# hacktor_watch2.net
KiCad netlist of a schematic drawn in EAGLE
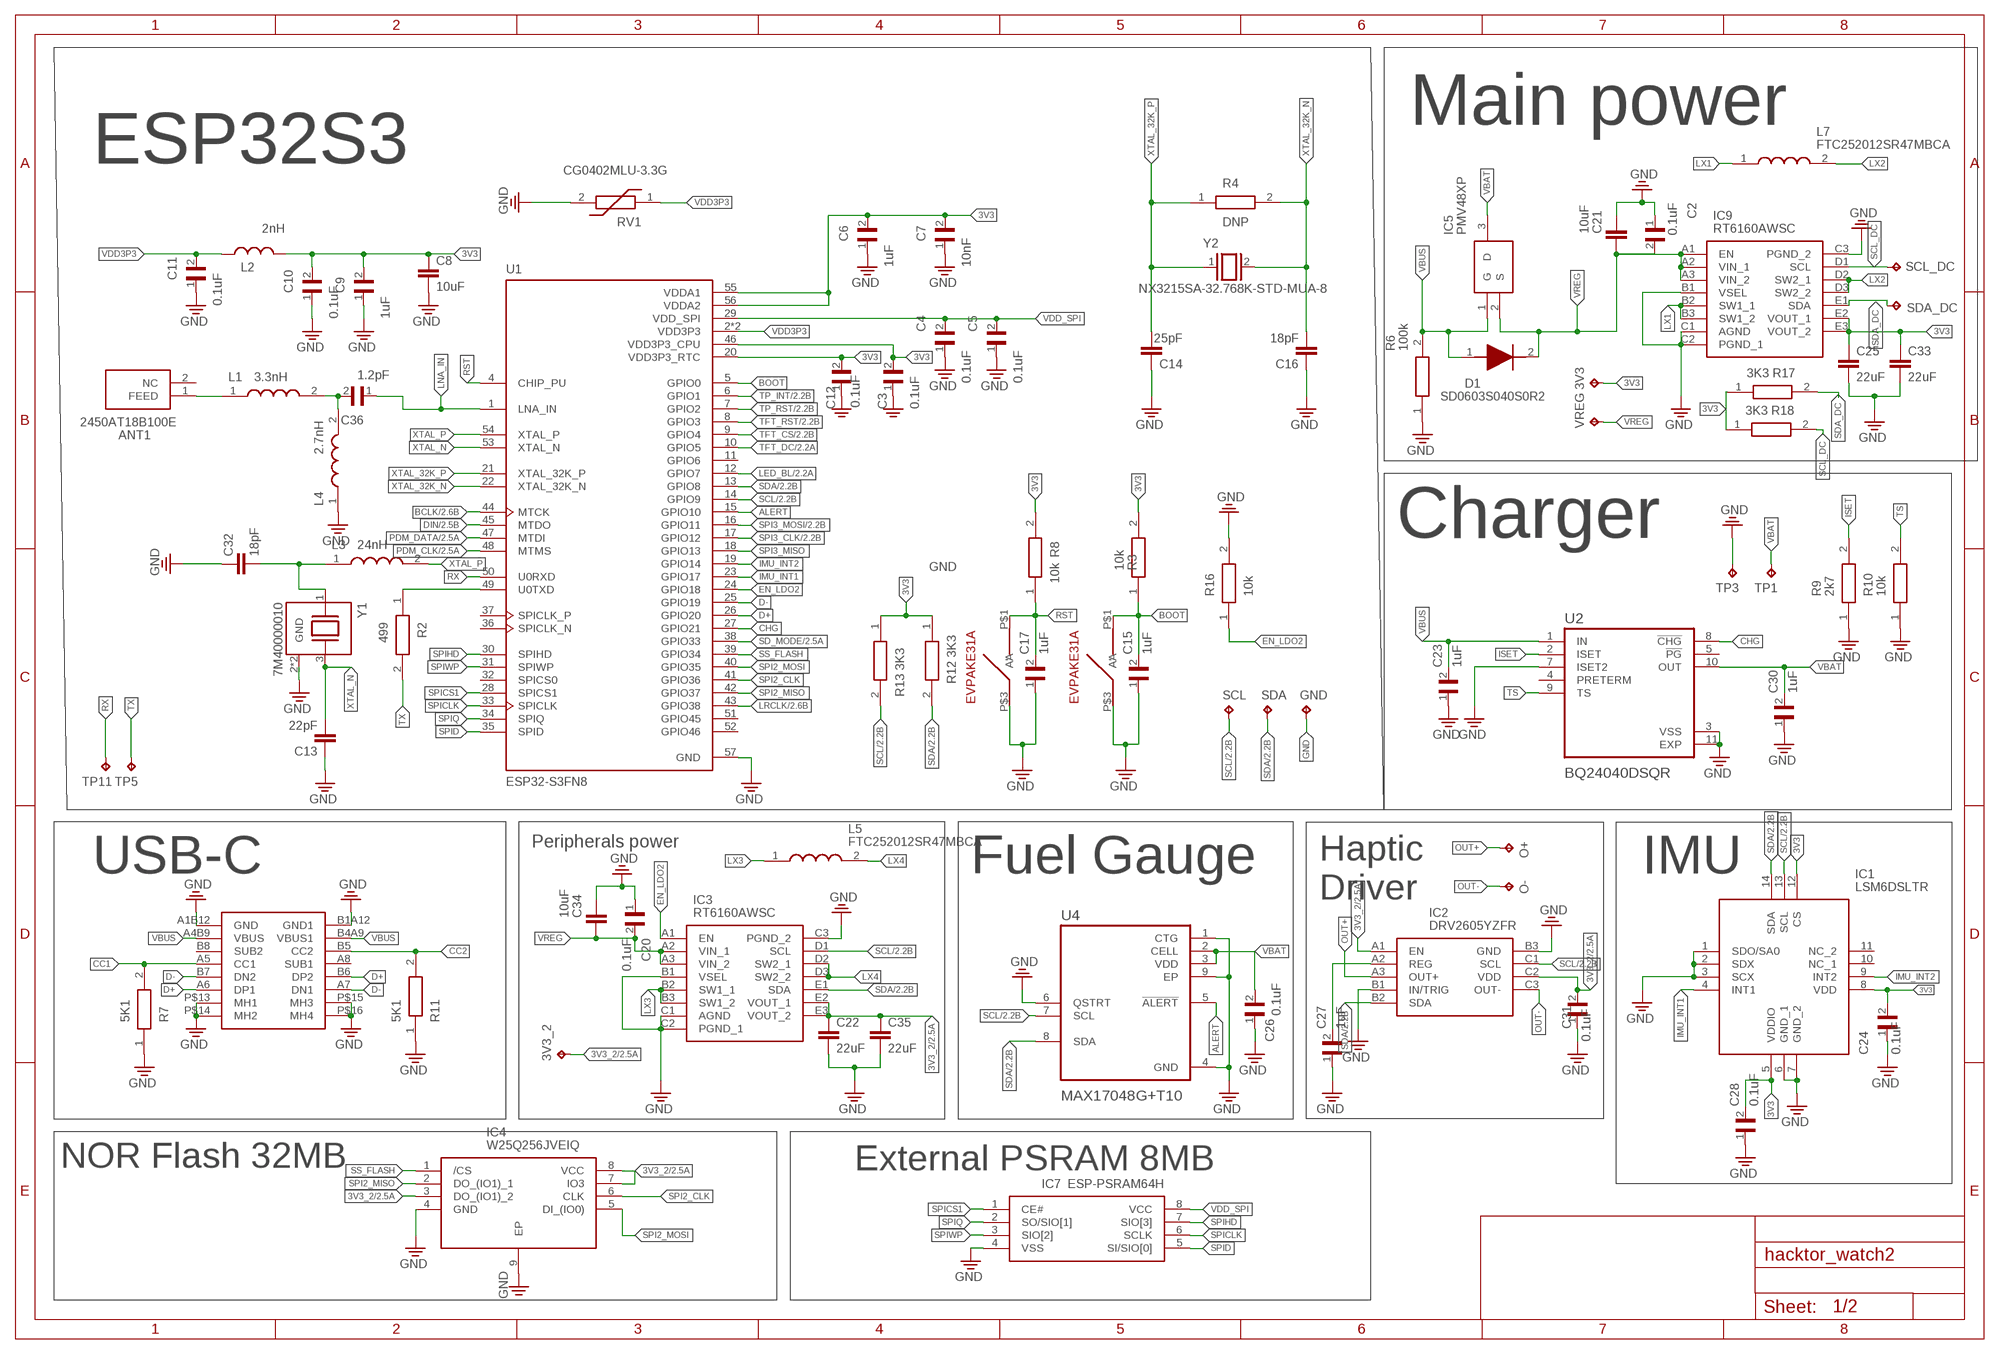
[diagram p0: schematic, sheet 1]
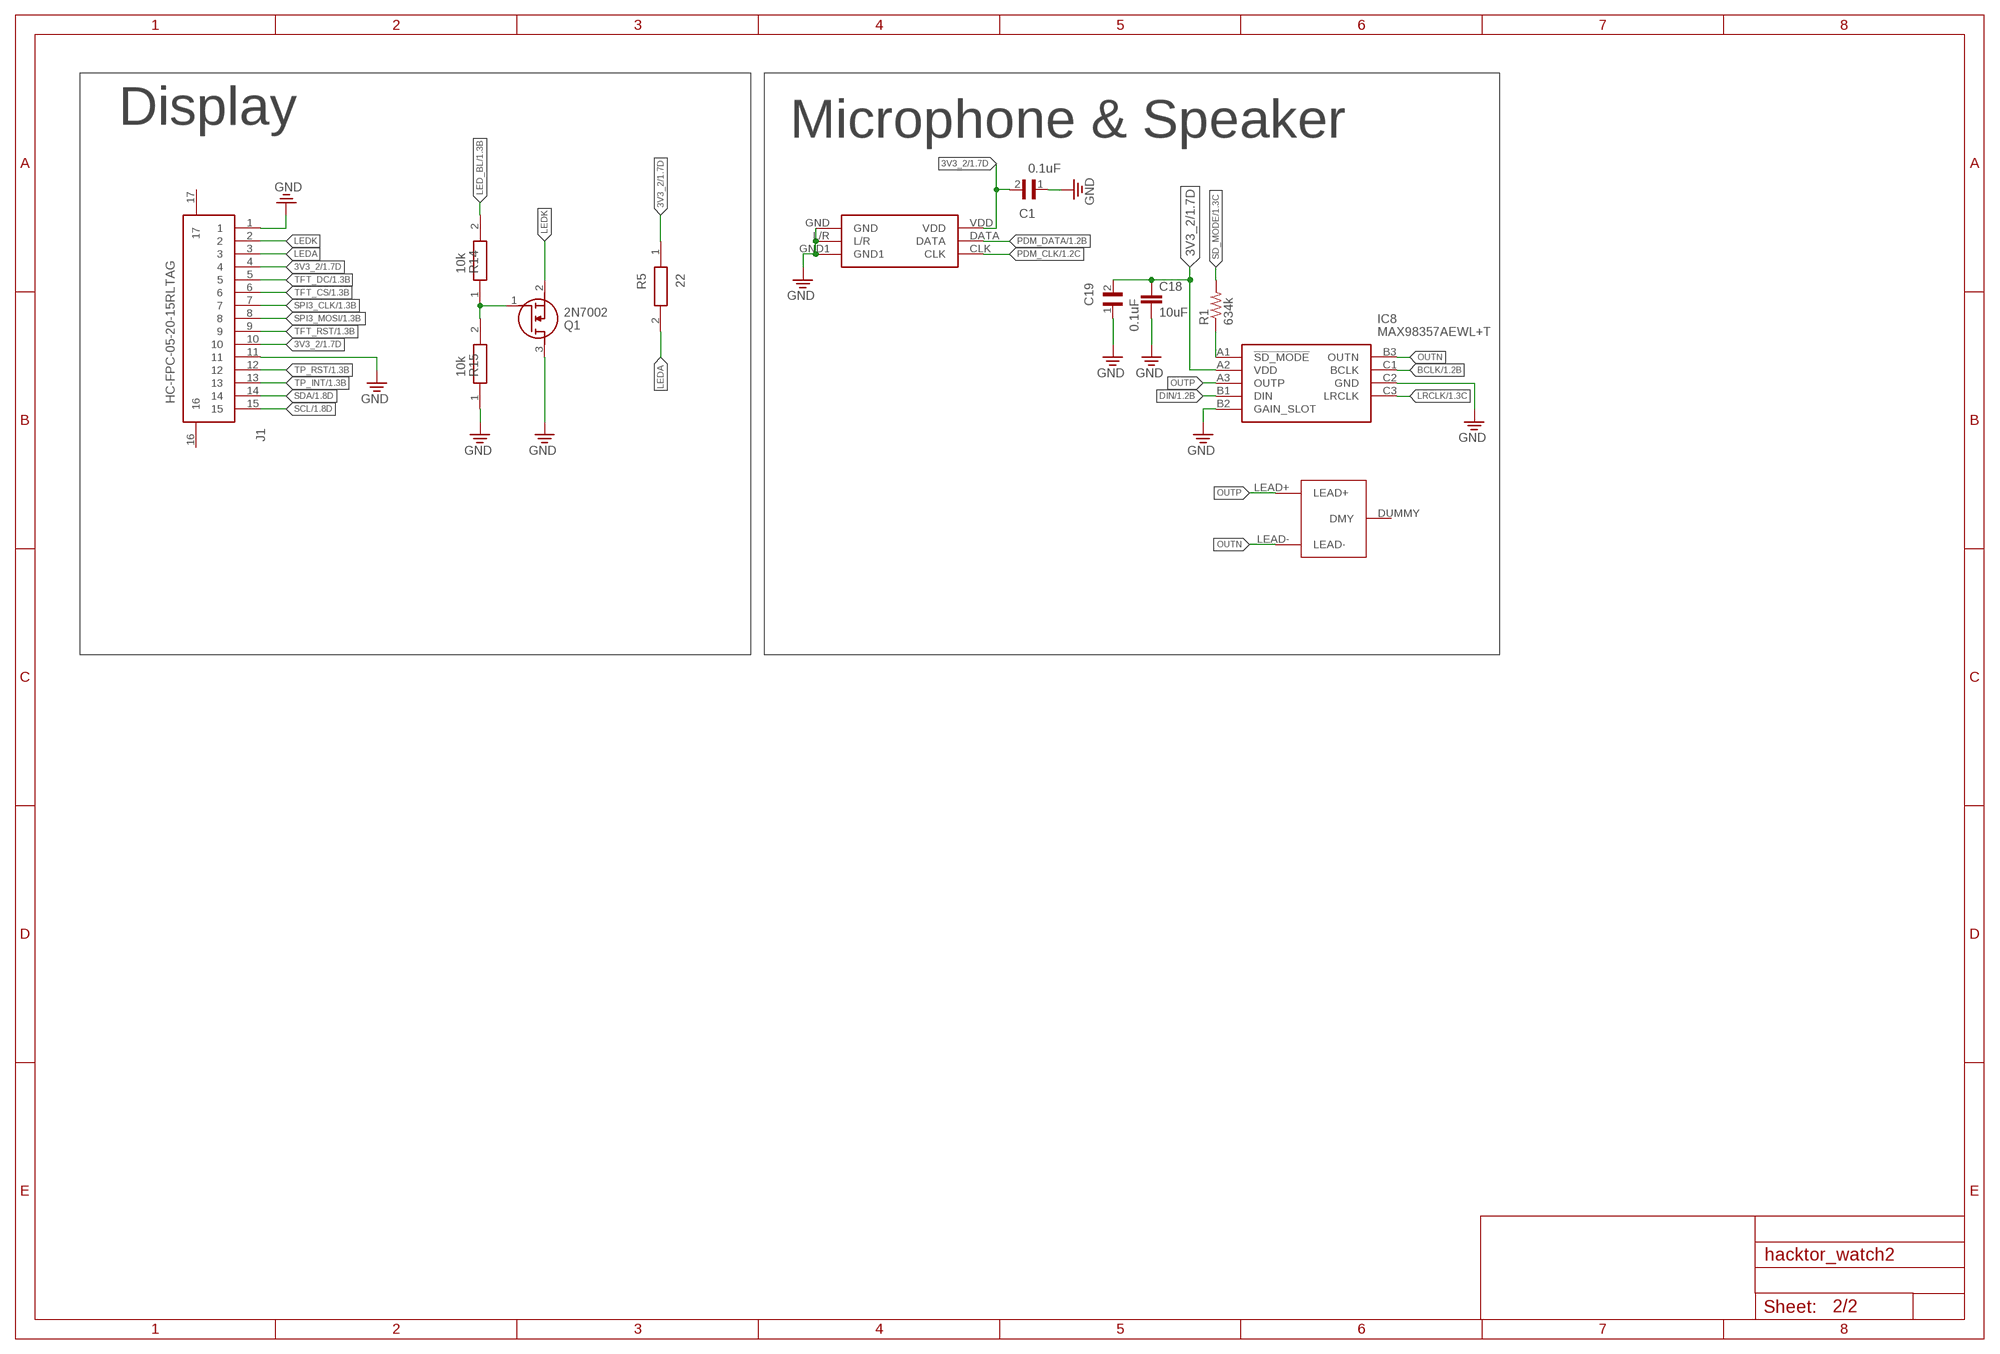
[diagram p1: schematic, sheet 2]

(export (version "E")
  (design (tool "Eeschema 10.0.6"))
  (components
    (comp (ref "C1")
      (value "0.1uF")
      (footprint "eagle-import:0201")
      (fields (field (name "SPICEPREFIX") "C"))
      (libsource (lib "eagle-import") (part "GRM011R60J152KE01L"))
    )
    (comp (ref "C18")
      (value "10uF")
      (footprint "eagle-import:0402")
      (libsource (lib "eagle-import") (part "CAP_0402"))
    )
    (comp (ref "C19")
      (value "0.1uF")
      (footprint "eagle-import:0201")
      (fields (field (name "SPICEPREFIX") "C"))
      (libsource (lib "eagle-import") (part "GRM011R60J152KE01L"))
    )
    (comp (ref "IC8")
      (value "MAX98357AEWL+T")
      (footprint "eagle-import:BGA9C40P3X3_144X135X69")
      (fields (field (name "MOUSER_PART_NUMBER") "700-MAX98357AEWL+T"))
      (libsource (lib "eagle-import") (part "MAX98357AEWL+T"))
    )
    (comp (ref "J1")
      (value "HC-FPC-05-20-15RLTAG")
      (footprint "eagle-import:HC-FPC-05-20-15RLTAG")
      (libsource (lib "eagle-import") (part "HC-FPC-05-20-15RLTAG"))
    )
    (comp (ref "Q1")
      (value "2N7002")
      (footprint "eagle-import:SOT96P240X120-3N")
      (fields (field (name "MOUSER_PART_NUMBER") "512-2N7002"))
      (libsource (lib "eagle-import") (part "2N7002"))
    )
    (comp (ref "R1")
      (value "634k")
      (footprint "eagle-import:0402")
      (libsource (lib "eagle-import") (part "RES_0402"))
    )
    (comp (ref "R5")
      (value "22")
      (footprint "eagle-import:0201")
      (fields (field (name "SPICEPREFIX") "R"))
      (libsource (lib "eagle-import") (part "CPF0201D7K68C1"))
    )
    (comp (ref "R14")
      (value "10k")
      (footprint "eagle-import:0201")
      (fields (field (name "SPICEPREFIX") "R"))
      (libsource (lib "eagle-import") (part "CPF0201D7K68C1"))
    )
    (comp (ref "R15")
      (value "10k")
      (footprint "eagle-import:0201")
      (fields (field (name "SPICEPREFIX") "R"))
      (libsource (lib "eagle-import") (part "CPF0201D7K68C1"))
    )
    (comp (ref "U$4")
      (value "TE054003-1")
      (footprint "eagle-import:TE054003-1")
      (libsource (lib "eagle-import") (part "TE054003-1"))
    )
    (comp (ref "U$6")
      (value "LMD2718T261-OA1")
      (footprint "eagle-import:LMD2718T261-OA1")
      (libsource (lib "eagle-import") (part "LMD2718T261-OA1"))
    )
    (comp (ref "3V3")
      (value "TPTP20R")
      (footprint "eagle-import:TP20R")
      (libsource (lib "eagle-import") (part "TPTP20R"))
    )
    (comp (ref "3V3_2")
      (value "TPTP20R")
      (footprint "eagle-import:TP20R")
      (libsource (lib "eagle-import") (part "TPTP20R"))
    )
    (comp (ref "ANT1")
      (value "2450AT18B100E")
      (footprint "eagle-import:ANTC3216X140N")
      (fields (field (name "MOUSER_PART_NUMBER") "609-2450AT18B100E"))
      (libsource (lib "eagle-import") (part "2450AT18B100E"))
    )
    (comp (ref "C2")
      (value "0.1uF")
      (footprint "eagle-import:0201")
      (fields (field (name "SPICEPREFIX") "C"))
      (libsource (lib "eagle-import") (part "GRM011R60J152KE01L"))
    )
    (comp (ref "C3")
      (value "0.1uF")
      (footprint "eagle-import:0201")
      (fields (field (name "SPICEPREFIX") "C"))
      (libsource (lib "eagle-import") (part "GRM011R60J152KE01L"))
    )
    (comp (ref "C4")
      (value "0.1uF")
      (footprint "eagle-import:0201")
      (fields (field (name "SPICEPREFIX") "C"))
      (libsource (lib "eagle-import") (part "GRM011R60J152KE01L"))
    )
    (comp (ref "C5")
      (value "0.1uF")
      (footprint "eagle-import:0201")
      (fields (field (name "SPICEPREFIX") "C"))
      (libsource (lib "eagle-import") (part "GRM011R60J152KE01L"))
    )
    (comp (ref "C6")
      (value "1uF")
      (footprint "eagle-import:0201")
      (fields (field (name "SPICEPREFIX") "C"))
      (libsource (lib "eagle-import") (part "GRM011R60J152KE01L"))
    )
    (comp (ref "C7")
      (value "10nF")
      (footprint "eagle-import:0201")
      (fields (field (name "SPICEPREFIX") "C"))
      (libsource (lib "eagle-import") (part "GRM011R60J152KE01L"))
    )
    (comp (ref "C8")
      (value "10uF")
      (footprint "eagle-import:0402")
      (libsource (lib "eagle-import") (part "CAP_0402"))
    )
    (comp (ref "C9")
      (value "1uF")
      (footprint "eagle-import:0201")
      (fields (field (name "SPICEPREFIX") "C"))
      (libsource (lib "eagle-import") (part "GRM011R60J152KE01L"))
    )
    (comp (ref "C10")
      (value "0.1uF")
      (footprint "eagle-import:0201")
      (fields (field (name "SPICEPREFIX") "C"))
      (libsource (lib "eagle-import") (part "GRM011R60J152KE01L"))
    )
    (comp (ref "C11")
      (value "0.1uF")
      (footprint "eagle-import:0201")
      (fields (field (name "SPICEPREFIX") "C"))
      (libsource (lib "eagle-import") (part "GRM011R60J152KE01L"))
    )
    (comp (ref "C12")
      (value "0.1uF")
      (footprint "eagle-import:0201")
      (fields (field (name "SPICEPREFIX") "C"))
      (libsource (lib "eagle-import") (part "GRM011R60J152KE01L"))
    )
    (comp (ref "C13")
      (value "22pF")
      (footprint "eagle-import:0402")
      (libsource (lib "eagle-import") (part "CAP_0402"))
    )
    (comp (ref "C14")
      (value "25pF")
      (footprint "eagle-import:0402")
      (libsource (lib "eagle-import") (part "CAP_0402"))
    )
    (comp (ref "C15")
      (value "1uF")
      (footprint "eagle-import:0201")
      (fields (field (name "SPICEPREFIX") "C"))
      (libsource (lib "eagle-import") (part "GRM011R60J152KE01L"))
    )
    (comp (ref "C16")
      (value "18pF")
      (footprint "eagle-import:0402")
      (libsource (lib "eagle-import") (part "CAP_0402"))
    )
    (comp (ref "C17")
      (value "1uF")
      (footprint "eagle-import:0201")
      (fields (field (name "SPICEPREFIX") "C"))
      (libsource (lib "eagle-import") (part "GRM011R60J152KE01L"))
    )
    (comp (ref "C20")
      (value "0.1uF")
      (footprint "eagle-import:0201")
      (fields (field (name "SPICEPREFIX") "C"))
      (libsource (lib "eagle-import") (part "GRM011R60J152KE01L"))
    )
    (comp (ref "C21")
      (value "10uF")
      (footprint "eagle-import:0402")
      (libsource (lib "eagle-import") (part "CAP_0402"))
    )
    (comp (ref "C22")
      (value "22uF")
      (footprint "eagle-import:0402")
      (libsource (lib "eagle-import") (part "CAP_0402"))
    )
    (comp (ref "C23")
      (value "1uF")
      (footprint "eagle-import:0201")
      (fields (field (name "SPICEPREFIX") "C"))
      (libsource (lib "eagle-import") (part "GRM011R60J152KE01L"))
    )
    (comp (ref "C24")
      (value "0.1uF")
      (footprint "eagle-import:0201")
      (fields (field (name "SPICEPREFIX") "C"))
      (libsource (lib "eagle-import") (part "GRM011R60J152KE01L"))
    )
    (comp (ref "C25")
      (value "22uF")
      (footprint "eagle-import:0402")
      (libsource (lib "eagle-import") (part "CAP_0402"))
    )
    (comp (ref "C26")
      (value "0.1uF")
      (footprint "eagle-import:0201")
      (fields (field (name "SPICEPREFIX") "C"))
      (libsource (lib "eagle-import") (part "GRM011R60J152KE01L"))
    )
    (comp (ref "C27")
      (value "1uF")
      (footprint "eagle-import:0201")
      (fields (field (name "SPICEPREFIX") "C"))
      (libsource (lib "eagle-import") (part "GRM011R60J152KE01L"))
    )
    (comp (ref "C28")
      (value "0.1uF")
      (footprint "eagle-import:0201")
      (fields (field (name "SPICEPREFIX") "C"))
      (libsource (lib "eagle-import") (part "GRM011R60J152KE01L"))
    )
    (comp (ref "C30")
      (value "1uF")
      (footprint "eagle-import:0201")
      (fields (field (name "SPICEPREFIX") "C"))
      (libsource (lib "eagle-import") (part "GRM011R60J152KE01L"))
    )
    (comp (ref "C31")
      (value "0.1uF")
      (footprint "eagle-import:0201")
      (fields (field (name "SPICEPREFIX") "C"))
      (libsource (lib "eagle-import") (part "GRM011R60J152KE01L"))
    )
    (comp (ref "C32")
      (value "18pF")
      (footprint "eagle-import:0402")
      (libsource (lib "eagle-import") (part "CAP_0402"))
    )
    (comp (ref "C33")
      (value "22uF")
      (footprint "eagle-import:0402")
      (libsource (lib "eagle-import") (part "CAP_0402"))
    )
    (comp (ref "C34")
      (value "10uF")
      (footprint "eagle-import:0402")
      (libsource (lib "eagle-import") (part "CAP_0402"))
    )
    (comp (ref "C35")
      (value "22uF")
      (footprint "eagle-import:0402")
      (libsource (lib "eagle-import") (part "CAP_0402"))
    )
    (comp (ref "C36")
      (value "1.2pF")
      (footprint "eagle-import:0201")
      (fields (field (name "SPICEPREFIX") "C"))
      (libsource (lib "eagle-import") (part "GRM011R60J152KE01L"))
    )
    (comp (ref "D1")
      (value "SD0603S040S0R2")
      (footprint "eagle-import:SD0603")
      (fields (field (name "MOUSER_PART_NUMBER") "581-SD0603S040S0R2"))
      (libsource (lib "eagle-import") (part "SD0603S040S0R2"))
    )
    (comp (ref "GND")
      (value "TPTP20R")
      (footprint "eagle-import:TP20R")
      (libsource (lib "eagle-import") (part "TPTP20R"))
    )
    (comp (ref "IC1")
      (value "LSM6DSLTR")
      (footprint "eagle-import:LSM6DSLTR")
      (fields (field (name "MF") "Analog Devices"))
      (libsource (lib "eagle-import") (part "LSM6DSLTR"))
    )
    (comp (ref "IC2")
      (value "DRV2605YZFR")
      (footprint "eagle-import:BGA9C50P3X3_144X144X62")
      (libsource (lib "eagle-import") (part "DRV2605YZFR"))
    )
    (comp (ref "IC3")
      (value "RT6160AWSC")
      (footprint "eagle-import:BGA15C40P3X5_140X230X60")
      (fields (field (name "MOUSER_PART_NUMBER") "835-RT6160AWSC"))
      (libsource (lib "eagle-import") (part "RT6160AWSC"))
    )
    (comp (ref "IC4")
      (value "W25Q256JVEIQ")
      (footprint "eagle-import:SON127P800X600X80-9N")
      (fields (field (name "MOUSER_PART_NUMBER") "454-W25Q256JVEIQ"))
      (libsource (lib "eagle-import") (part "W25Q256JVEIQ"))
    )
    (comp (ref "IC5")
      (value "PMV48XP")
      (footprint "eagle-import:SOT95P230X110-3N")
      (libsource (lib "eagle-import") (part "PMV48XP"))
    )
    (comp (ref "IC7")
      (value "ESP-PSRAM64H")
      (footprint "eagle-import:SOIC127P600X175-8N")
      (libsource (lib "eagle-import") (part "ESP-PSRAM64H"))
    )
    (comp (ref "IC9")
      (value "RT6160AWSC")
      (footprint "eagle-import:BGA15C40P3X5_140X230X60")
      (fields (field (name "MOUSER_PART_NUMBER") "835-RT6160AWSC"))
      (libsource (lib "eagle-import") (part "RT6160AWSC"))
    )
    (comp (ref "L1")
      (value "3.3nH")
      (footprint "eagle-import:LQP15MN10NG02D")
      (fields (field (name "ARROW_PART_NUMBER") "LQP15MN5N6B02D") (field (name "SPICEPREFIX") "L"))
      (libsource (lib "eagle-import") (part "LQP15MN5N6B02D"))
    )
    (comp (ref "L2")
      (value "2nH")
      (footprint "eagle-import:INDC1006X60N")
      (fields (field (name "SPICEPREFIX") "L"))
      (libsource (lib "eagle-import") (part "INDUCTORCHIP-0402(1006-METRIC)_"))
    )
    (comp (ref "L3")
      (value "24nH")
      (footprint "eagle-import:LQP15MN10NG02D")
      (fields (field (name "ARROW_PART_NUMBER") "LQP15MN5N6B02D") (field (name "SPICEPREFIX") "L"))
      (libsource (lib "eagle-import") (part "LQP15MN5N6B02D"))
    )
    (comp (ref "L4")
      (value "2.7nH")
      (footprint "eagle-import:LQP15MN10NG02D")
      (fields (field (name "ARROW_PART_NUMBER") "LQP15MN5N6B02D") (field (name "SPICEPREFIX") "L"))
      (libsource (lib "eagle-import") (part "LQP15MN5N6B02D"))
    )
    (comp (ref "L5")
      (value "FTC252012SR47MBCA")
      (footprint "eagle-import:INDC2016X100N")
      (libsource (lib "eagle-import") (part "FTC252012SR47MBCA"))
    )
    (comp (ref "L7")
      (value "FTC252012SR47MBCA")
      (footprint "eagle-import:INDC2016X100N")
      (libsource (lib "eagle-import") (part "FTC252012SR47MBCA"))
    )
    (comp (ref "O+")
      (value "TPTP20R")
      (footprint "eagle-import:TP20R")
      (libsource (lib "eagle-import") (part "TPTP20R"))
    )
    (comp (ref "O-")
      (value "TPTP20R")
      (footprint "eagle-import:TP20R")
      (libsource (lib "eagle-import") (part "TPTP20R"))
    )
    (comp (ref "R2")
      (value "499")
      (footprint "eagle-import:0201")
      (fields (field (name "SPICEPREFIX") "R"))
      (libsource (lib "eagle-import") (part "CPF0201D7K68C1"))
    )
    (comp (ref "R3")
      (value "10k")
      (footprint "eagle-import:0201")
      (fields (field (name "SPICEPREFIX") "R"))
      (libsource (lib "eagle-import") (part "CPF0201D7K68C1"))
    )
    (comp (ref "R4")
      (value "DNP")
      (footprint "eagle-import:0201")
      (fields (field (name "SPICEPREFIX") "R"))
      (libsource (lib "eagle-import") (part "CPF0201D7K68C1"))
    )
    (comp (ref "R6")
      (value "100k")
      (footprint "eagle-import:0201")
      (libsource (lib "eagle-import") (part "CPF0201D7K68C1"))
    )
    (comp (ref "R7")
      (value "5K1")
      (footprint "eagle-import:0201")
      (fields (field (name "SPICEPREFIX") "R"))
      (libsource (lib "eagle-import") (part "CPF0201D7K68C1"))
    )
    (comp (ref "R8")
      (value "10k")
      (footprint "eagle-import:0201")
      (fields (field (name "SPICEPREFIX") "R"))
      (libsource (lib "eagle-import") (part "CPF0201D7K68C1"))
    )
    (comp (ref "R9")
      (value "2k7")
      (footprint "eagle-import:0201")
      (libsource (lib "eagle-import") (part "CPF0201D7K68C1"))
    )
    (comp (ref "R10")
      (value "10k")
      (footprint "eagle-import:0201")
      (libsource (lib "eagle-import") (part "CPF0201D7K68C1"))
    )
    (comp (ref "R11")
      (value "5K1")
      (footprint "eagle-import:0201")
      (fields (field (name "SPICEPREFIX") "R"))
      (libsource (lib "eagle-import") (part "CPF0201D7K68C1"))
    )
    (comp (ref "R12")
      (value "3K3")
      (footprint "eagle-import:0201")
      (fields (field (name "SPICEPREFIX") "R"))
      (libsource (lib "eagle-import") (part "CPF0201D7K68C1"))
    )
    (comp (ref "R13")
      (value "3K3")
      (footprint "eagle-import:0201")
      (fields (field (name "SPICEPREFIX") "R"))
      (libsource (lib "eagle-import") (part "CPF0201D7K68C1"))
    )
    (comp (ref "R16")
      (value "10k")
      (footprint "eagle-import:0201")
      (fields (field (name "SPICEPREFIX") "R"))
      (libsource (lib "eagle-import") (part "CPF0201D7K68C1"))
    )
    (comp (ref "R17")
      (value "3K3")
      (footprint "eagle-import:0201")
      (fields (field (name "SPICEPREFIX") "R"))
      (libsource (lib "eagle-import") (part "CPF0201D7K68C1"))
    )
    (comp (ref "R18")
      (value "3K3")
      (footprint "eagle-import:0201")
      (fields (field (name "SPICEPREFIX") "R"))
      (libsource (lib "eagle-import") (part "CPF0201D7K68C1"))
    )
    (comp (ref "RV1")
      (value "CG0402MLU-3.3G")
      (footprint "eagle-import:VARC1005X41N")
      (fields (field (name "MOUSER_PART_NUMBER") "652-CG0402MLU-3.3G"))
      (libsource (lib "eagle-import") (part "CG0402MLU-3.3G"))
    )
    (comp (ref "SCL")
      (value "TPTP20R")
      (footprint "eagle-import:TP20R")
      (libsource (lib "eagle-import") (part "TPTP20R"))
    )
    (comp (ref "SCL_DC")
      (value "TPTP20R")
      (footprint "eagle-import:TP20R")
      (libsource (lib "eagle-import") (part "TPTP20R"))
    )
    (comp (ref "SDA")
      (value "TPTP20R")
      (footprint "eagle-import:TP20R")
      (libsource (lib "eagle-import") (part "TPTP20R"))
    )
    (comp (ref "SDA_DC")
      (value "TPTP20R")
      (footprint "eagle-import:TP20R")
      (libsource (lib "eagle-import") (part "TPTP20R"))
    )
    (comp (ref "TP1")
      (value "TPTP20R")
      (footprint "eagle-import:TP20R")
      (libsource (lib "eagle-import") (part "TPTP20R"))
    )
    (comp (ref "TP3")
      (value "TPTP20R")
      (footprint "eagle-import:TP20R")
      (libsource (lib "eagle-import") (part "TPTP20R"))
    )
    (comp (ref "TP5")
      (value "TPTP20R")
      (footprint "eagle-import:TP20R")
      (libsource (lib "eagle-import") (part "TPTP20R"))
    )
    (comp (ref "TP11")
      (value "TPTP20R")
      (footprint "eagle-import:TP20R")
      (libsource (lib "eagle-import") (part "TPTP20R"))
    )
    (comp (ref "U$1")
      (value "EVPAKE31A")
      (footprint "eagle-import:EVPAKE31A")
      (libsource (lib "eagle-import") (part "EVPAKE31A"))
    )
    (comp (ref "U$3")
      (value "EVPAKE31A")
      (footprint "eagle-import:EVPAKE31A")
      (libsource (lib "eagle-import") (part "EVPAKE31A"))
    )
    (comp (ref "U$5")
      (value "TYPE-C16PCB0.8073")
      (footprint "eagle-import:TYPE-C16PCB0.8073")
      (libsource (lib "eagle-import") (part "TYPE-C16PCB0.8073"))
    )
    (comp (ref "U1")
      (value "ESP32-S3FN8")
      (footprint "eagle-import:QFN40P700X700X90-57N")
      (fields (field (name "MF") "Espressif Systems"))
      (libsource (lib "eagle-import") (part "ESP32-S3FN8"))
    )
    (comp (ref "U2")
      (value "BQ24040DSQR")
      (footprint "eagle-import:SON40P200X200X80-11N")
      (fields (field (name "MF") "Texas Instruments"))
      (libsource (lib "eagle-import") (part "BQ24040DSQR"))
    )
    (comp (ref "U4")
      (value "MAX17048G+T10")
      (footprint "eagle-import:SON50P200X200X80-9N")
      (fields (field (name "MF") "Analog Devices"))
      (libsource (lib "eagle-import") (part "MAX17048G+T10"))
    )
    (comp (ref "VREG")
      (value "TPTP20R")
      (footprint "eagle-import:TP20R")
      (libsource (lib "eagle-import") (part "TPTP20R"))
    )
    (comp (ref "Y1")
      (value "7M40000010")
      (footprint "eagle-import:XTAL_7M40000010")
      (fields (field (name "MF") "TXC CORPORATION") (field (name "SPICEPREFIX") "J"))
      (libsource (lib "eagle-import") (part "7M40000010"))
    )
    (comp (ref "Y2")
      (value "NX3215SA-32.768K-STD-MUA-8")
      (footprint "eagle-import:XTAL_NX3215SA-32.768K-STD-MUA-8")
      (fields (field (name "MF") "NDK America,") (field (name "SPICEPREFIX") "B"))
      (libsource (lib "eagle-import") (part "NX3215SA-32.768K-STD-MUA-8"))
    )
  )
  (nets
    (net (code "1") (name "3V3") (class "Default")
      (node (ref "3V3") (pin "TP") (pinfunction "TP_TP") (pintype "input"))
      (node (ref "C10") (pin "2") (pinfunction "2_2") (pintype "passive"))
      (node (ref "C12") (pin "2") (pinfunction "2_2") (pintype "passive"))
      (node (ref "C24") (pin "2") (pinfunction "2_2") (pintype "passive"))
      (node (ref "C25") (pin "1") (pinfunction "1_1") (pintype "passive"))
      (node (ref "C28") (pin "2") (pinfunction "2_2") (pintype "passive"))
      (node (ref "C3") (pin "2") (pinfunction "2_2") (pintype "passive"))
      (node (ref "C33") (pin "1") (pinfunction "1_1") (pintype "passive"))
      (node (ref "C6") (pin "2") (pinfunction "2_2") (pintype "passive"))
      (node (ref "C7") (pin "2") (pinfunction "2_2") (pintype "passive"))
      (node (ref "C8") (pin "1") (pinfunction "1_1") (pintype "passive"))
      (node (ref "C9") (pin "2") (pinfunction "2_2") (pintype "passive"))
      (node (ref "IC1") (pin "12") (pinfunction "CS_12") (pintype "bidirectional"))
      (node (ref "IC1") (pin "5") (pinfunction "VDDIO_5") (pintype "bidirectional"))
      (node (ref "IC1") (pin "8") (pinfunction "VDD_8") (pintype "bidirectional"))
      (node (ref "IC9") (pin "E2") (pinfunction "VOUT_1_E2") (pintype "bidirectional"))
      (node (ref "IC9") (pin "E3") (pinfunction "VOUT_2_E3") (pintype "bidirectional"))
      (node (ref "L2") (pin "2") (pinfunction "2_2") (pintype "passive"))
      (node (ref "R12") (pin "1") (pinfunction "1_1") (pintype "bidirectional"))
      (node (ref "R13") (pin "1") (pinfunction "1_1") (pintype "bidirectional"))
      (node (ref "R17") (pin "1") (pinfunction "1_1") (pintype "bidirectional"))
      (node (ref "R18") (pin "1") (pinfunction "1_1") (pintype "bidirectional"))
      (node (ref "R3") (pin "2") (pinfunction "2_2") (pintype "bidirectional"))
      (node (ref "R8") (pin "2") (pinfunction "2_2") (pintype "bidirectional"))
      (node (ref "U1") (pin "20") (pinfunction "VDD3P3_RTC_20") (pintype "power_in"))
      (node (ref "U1") (pin "46") (pinfunction "VDD3P3_CPU_46") (pintype "power_in"))
      (node (ref "U1") (pin "55") (pinfunction "VDDA1_55") (pintype "power_in"))
      (node (ref "U1") (pin "56") (pinfunction "VDDA2_56") (pintype "power_in"))
    )
    (net (code "2") (name "3V3_2") (class "Default")
      (node (ref "3V3_2") (pin "TP") (pinfunction "TP_TP") (pintype "input"))
      (node (ref "C1") (pin "2") (pinfunction "2_2") (pintype "passive"))
      (node (ref "C18") (pin "1") (pinfunction "1_1") (pintype "passive"))
      (node (ref "C19") (pin "2") (pinfunction "2_2") (pintype "passive"))
      (node (ref "C22") (pin "1") (pinfunction "1_1") (pintype "passive"))
      (node (ref "C31") (pin "2") (pinfunction "2_2") (pintype "passive"))
      (node (ref "C35") (pin "1") (pinfunction "1_1") (pintype "passive"))
      (node (ref "IC2") (pin "A1") (pinfunction "EN_A1") (pintype "bidirectional"))
      (node (ref "IC2") (pin "C2") (pinfunction "VDD_C2") (pintype "bidirectional"))
      (node (ref "IC3") (pin "E2") (pinfunction "VOUT_1_E2") (pintype "bidirectional"))
      (node (ref "IC3") (pin "E3") (pinfunction "VOUT_2_E3") (pintype "bidirectional"))
      (node (ref "IC4") (pin "3") (pinfunction "DO_(IO1)_2_3") (pintype "bidirectional"))
      (node (ref "IC4") (pin "7") (pinfunction "IO3_7") (pintype "bidirectional"))
      (node (ref "IC4") (pin "8") (pinfunction "VCC_8") (pintype "bidirectional"))
      (node (ref "IC8") (pin "A2") (pinfunction "VDD_A2") (pintype "bidirectional"))
      (node (ref "J1") (pin "10") (pinfunction "10_10") (pintype "bidirectional"))
      (node (ref "J1") (pin "4") (pinfunction "4_4") (pintype "bidirectional"))
      (node (ref "R5") (pin "1") (pinfunction "1_1") (pintype "bidirectional"))
      (node (ref "U$6") (pin "VDD") (pinfunction "VDD_VDD") (pintype "bidirectional"))
    )
    (net (code "3") (name "ALERT") (class "Default")
      (node (ref "U1") (pin "15") (pinfunction "GPIO10_15") (pintype "bidirectional"))
      (node (ref "U4") (pin "5") (pinfunction "~{ALERT}_5") (pintype "output"))
    )
    (net (code "4") (name "BCLK") (class "Default")
      (node (ref "IC8") (pin "C1") (pinfunction "BCLK_C1") (pintype "bidirectional"))
      (node (ref "U1") (pin "44") (pinfunction "MTCK_44") (pintype "bidirectional"))
    )
    (net (code "5") (name "BOOT") (class "Default")
      (node (ref "C15") (pin "2") (pinfunction "2_2") (pintype "passive"))
      (node (ref "R3") (pin "1") (pinfunction "1_1") (pintype "bidirectional"))
      (node (ref "U$1") (pin "P$1") (pinfunction "A_P$1") (pintype "bidirectional"))
      (node (ref "U1") (pin "5") (pinfunction "GPIO0_5") (pintype "bidirectional"))
    )
    (net (code "6") (name "CC1") (class "Default")
      (node (ref "R7") (pin "2") (pinfunction "2_2") (pintype "bidirectional"))
      (node (ref "U$5") (pin "A5") (pinfunction "CC1_A5") (pintype "bidirectional"))
    )
    (net (code "7") (name "CC2") (class "Default")
      (node (ref "R11") (pin "2") (pinfunction "2_2") (pintype "bidirectional"))
      (node (ref "U$5") (pin "B5") (pinfunction "CC2_B5") (pintype "bidirectional"))
    )
    (net (code "8") (name "CHG") (class "Default")
      (node (ref "U1") (pin "27") (pinfunction "GPIO21_27") (pintype "bidirectional"))
      (node (ref "U2") (pin "8") (pinfunction "~{CHG}_8") (pintype "output"))
    )
    (net (code "9") (name "D+") (class "Default")
      (node (ref "U$5") (pin "A6") (pinfunction "DP1_A6") (pintype "bidirectional"))
      (node (ref "U$5") (pin "B6") (pinfunction "DP2_B6") (pintype "bidirectional"))
      (node (ref "U1") (pin "26") (pinfunction "GPIO20_26") (pintype "bidirectional"))
    )
    (net (code "10") (name "D-") (class "Default")
      (node (ref "U$5") (pin "A7") (pinfunction "DN1_A7") (pintype "bidirectional"))
      (node (ref "U$5") (pin "B7") (pinfunction "DN2_B7") (pintype "bidirectional"))
      (node (ref "U1") (pin "25") (pinfunction "GPIO19_25") (pintype "bidirectional"))
    )
    (net (code "11") (name "DIN") (class "Default")
      (node (ref "IC8") (pin "B1") (pinfunction "DIN_B1") (pintype "bidirectional"))
      (node (ref "U1") (pin "45") (pinfunction "MTDO_45") (pintype "bidirectional"))
    )
    (net (code "12") (name "EN_LDO2") (class "Default")
      (node (ref "IC3") (pin "A1") (pinfunction "EN_A1") (pintype "bidirectional"))
      (node (ref "R16") (pin "1") (pinfunction "1_1") (pintype "bidirectional"))
      (node (ref "U1") (pin "24") (pinfunction "GPIO18_24") (pintype "bidirectional"))
    )
    (net (code "13") (name "GND") (class "Default")
      (node (ref "C1") (pin "1") (pinfunction "1_1") (pintype "passive"))
      (node (ref "C10") (pin "1") (pinfunction "1_1") (pintype "passive"))
      (node (ref "C11") (pin "1") (pinfunction "1_1") (pintype "passive"))
      (node (ref "C12") (pin "1") (pinfunction "1_1") (pintype "passive"))
      (node (ref "C13") (pin "1") (pinfunction "1_1") (pintype "passive"))
      (node (ref "C14") (pin "1") (pinfunction "1_1") (pintype "passive"))
      (node (ref "C15") (pin "1") (pinfunction "1_1") (pintype "passive"))
      (node (ref "C16") (pin "1") (pinfunction "1_1") (pintype "passive"))
      (node (ref "C17") (pin "1") (pinfunction "1_1") (pintype "passive"))
      (node (ref "C18") (pin "2") (pinfunction "2_2") (pintype "passive"))
      (node (ref "C19") (pin "1") (pinfunction "1_1") (pintype "passive"))
      (node (ref "C2") (pin "1") (pinfunction "1_1") (pintype "passive"))
      (node (ref "C20") (pin "1") (pinfunction "1_1") (pintype "passive"))
      (node (ref "C21") (pin "1") (pinfunction "1_1") (pintype "passive"))
      (node (ref "C22") (pin "2") (pinfunction "2_2") (pintype "passive"))
      (node (ref "C23") (pin "1") (pinfunction "1_1") (pintype "passive"))
      (node (ref "C24") (pin "1") (pinfunction "1_1") (pintype "passive"))
      (node (ref "C25") (pin "2") (pinfunction "2_2") (pintype "passive"))
      (node (ref "C26") (pin "1") (pinfunction "1_1") (pintype "passive"))
      (node (ref "C27") (pin "1") (pinfunction "1_1") (pintype "passive"))
      (node (ref "C28") (pin "1") (pinfunction "1_1") (pintype "passive"))
      (node (ref "C3") (pin "1") (pinfunction "1_1") (pintype "passive"))
      (node (ref "C30") (pin "1") (pinfunction "1_1") (pintype "passive"))
      (node (ref "C31") (pin "1") (pinfunction "1_1") (pintype "passive"))
      (node (ref "C32") (pin "1") (pinfunction "1_1") (pintype "passive"))
      (node (ref "C33") (pin "2") (pinfunction "2_2") (pintype "passive"))
      (node (ref "C34") (pin "1") (pinfunction "1_1") (pintype "passive"))
      (node (ref "C35") (pin "2") (pinfunction "2_2") (pintype "passive"))
      (node (ref "C4") (pin "1") (pinfunction "1_1") (pintype "passive"))
      (node (ref "C5") (pin "1") (pinfunction "1_1") (pintype "passive"))
      (node (ref "C6") (pin "1") (pinfunction "1_1") (pintype "passive"))
      (node (ref "C7") (pin "1") (pinfunction "1_1") (pintype "passive"))
      (node (ref "C8") (pin "2") (pinfunction "2_2") (pintype "passive"))
      (node (ref "C9") (pin "1") (pinfunction "1_1") (pintype "passive"))
      (node (ref "GND") (pin "TP") (pinfunction "TP_TP") (pintype "input"))
      (node (ref "IC1") (pin "1") (pinfunction "SDO/SA0_1") (pintype "bidirectional"))
      (node (ref "IC1") (pin "2") (pinfunction "SDX_2") (pintype "bidirectional"))
      (node (ref "IC1") (pin "3") (pinfunction "SCX_3") (pintype "bidirectional"))
      (node (ref "IC1") (pin "6") (pinfunction "GND_1_6") (pintype "bidirectional"))
      (node (ref "IC1") (pin "7") (pinfunction "GND_2_7") (pintype "bidirectional"))
      (node (ref "IC2") (pin "B1") (pinfunction "IN/TRIG_B1") (pintype "bidirectional"))
      (node (ref "IC2") (pin "B3") (pinfunction "GND_B3") (pintype "bidirectional"))
      (node (ref "IC3") (pin "B1") (pinfunction "VSEL_B1") (pintype "bidirectional"))
      (node (ref "IC3") (pin "C1") (pinfunction "AGND_C1") (pintype "bidirectional"))
      (node (ref "IC3") (pin "C2") (pinfunction "PGND_1_C2") (pintype "bidirectional"))
      (node (ref "IC3") (pin "C3") (pinfunction "PGND_2_C3") (pintype "bidirectional"))
      (node (ref "IC4") (pin "4") (pinfunction "GND_4") (pintype "bidirectional"))
      (node (ref "IC4") (pin "9") (pinfunction "EP_9") (pintype "bidirectional"))
      (node (ref "IC7") (pin "4") (pinfunction "VSS_4") (pintype "power_in"))
      (node (ref "IC8") (pin "B2") (pinfunction "GAIN_SLOT_B2") (pintype "bidirectional"))
      (node (ref "IC8") (pin "C2") (pinfunction "GND_C2") (pintype "bidirectional"))
      (node (ref "IC9") (pin "B1") (pinfunction "VSEL_B1") (pintype "bidirectional"))
      (node (ref "IC9") (pin "C1") (pinfunction "AGND_C1") (pintype "bidirectional"))
      (node (ref "IC9") (pin "C2") (pinfunction "PGND_1_C2") (pintype "bidirectional"))
      (node (ref "IC9") (pin "C3") (pinfunction "PGND_2_C3") (pintype "bidirectional"))
      (node (ref "J1") (pin "1") (pinfunction "1_1") (pintype "bidirectional"))
      (node (ref "J1") (pin "11") (pinfunction "11_11") (pintype "bidirectional"))
      (node (ref "L4") (pin "1") (pinfunction "1_1") (pintype "bidirectional"))
      (node (ref "Q1") (pin "3") (pinfunction "D_3") (pintype "bidirectional"))
      (node (ref "R10") (pin "1") (pinfunction "1_1") (pintype "bidirectional"))
      (node (ref "R11") (pin "1") (pinfunction "1_1") (pintype "bidirectional"))
      (node (ref "R15") (pin "1") (pinfunction "1_1") (pintype "bidirectional"))
      (node (ref "R16") (pin "2") (pinfunction "2_2") (pintype "bidirectional"))
      (node (ref "R6") (pin "1") (pinfunction "1_1") (pintype "bidirectional"))
      (node (ref "R7") (pin "1") (pinfunction "1_1") (pintype "bidirectional"))
      (node (ref "R9") (pin "1") (pinfunction "1_1") (pintype "bidirectional"))
      (node (ref "RV1") (pin "2") (pinfunction "2_2") (pintype "bidirectional"))
      (node (ref "TP3") (pin "TP") (pinfunction "TP_TP") (pintype "input"))
      (node (ref "U$1") (pin "P$3") (pinfunction "A'_P$3") (pintype "bidirectional"))
      (node (ref "U$3") (pin "P$3") (pinfunction "A'_P$3") (pintype "bidirectional"))
      (node (ref "U$5") (pin "A1B12") (pinfunction "GND_A1B12") (pintype "bidirectional"))
      (node (ref "U$5") (pin "B1A12") (pinfunction "GND1_B1A12") (pintype "bidirectional"))
      (node (ref "U$5") (pin "P$13") (pinfunction "MH1_P$13") (pintype "bidirectional"))
      (node (ref "U$5") (pin "P$14") (pinfunction "MH2_P$14") (pintype "bidirectional"))
      (node (ref "U$5") (pin "P$15") (pinfunction "MH3_P$15") (pintype "bidirectional"))
      (node (ref "U$5") (pin "P$16") (pinfunction "MH4_P$16") (pintype "bidirectional"))
      (node (ref "U$6") (pin "GND") (pinfunction "GND_GND") (pintype "bidirectional"))
      (node (ref "U$6") (pin "GND1") (pinfunction "GND1_GND1") (pintype "bidirectional"))
      (node (ref "U$6") (pin "L/R") (pinfunction "L/R_L/R") (pintype "bidirectional"))
      (node (ref "U1") (pin "57") (pinfunction "GND_57") (pintype "power_in"))
      (node (ref "U2") (pin "11") (pinfunction "EXP_11") (pintype "power_in"))
      (node (ref "U2") (pin "3") (pinfunction "VSS_3") (pintype "power_in"))
      (node (ref "U2") (pin "7") (pinfunction "ISET2_7") (pintype "input"))
      (node (ref "U4") (pin "1") (pinfunction "CTG_1") (pintype "power_in"))
      (node (ref "U4") (pin "4") (pinfunction "GND_4") (pintype "power_in"))
      (node (ref "U4") (pin "6") (pinfunction "QSTRT_6") (pintype "input"))
      (node (ref "U4") (pin "9") (pinfunction "EP_9") (pintype "power_in"))
      (node (ref "Y1") (pin "2") (pinfunction "GND_2") (pintype "power_in"))
      (node (ref "Y1") (pin "4") (pinfunction "GND_4") (pintype "power_in"))
    )
    (net (code "14") (name "IMU_INT1") (class "Default")
      (node (ref "IC1") (pin "4") (pinfunction "INT1_4") (pintype "bidirectional"))
      (node (ref "U1") (pin "23") (pinfunction "GPIO17_23") (pintype "bidirectional"))
    )
    (net (code "15") (name "IMU_INT2") (class "Default")
      (node (ref "IC1") (pin "9") (pinfunction "INT2_9") (pintype "bidirectional"))
      (node (ref "U1") (pin "19") (pinfunction "GPIO14_19") (pintype "bidirectional"))
    )
    (net (code "16") (name "ISET") (class "Default")
      (node (ref "R9") (pin "2") (pinfunction "2_2") (pintype "bidirectional"))
      (node (ref "U2") (pin "2") (pinfunction "ISET_2") (pintype "input"))
    )
    (net (code "17") (name "LEDA") (class "Default")
      (node (ref "J1") (pin "3") (pinfunction "3_3") (pintype "bidirectional"))
      (node (ref "R5") (pin "2") (pinfunction "2_2") (pintype "bidirectional"))
    )
    (net (code "18") (name "LEDK") (class "Default")
      (node (ref "J1") (pin "2") (pinfunction "2_2") (pintype "bidirectional"))
      (node (ref "Q1") (pin "2") (pinfunction "S_2") (pintype "bidirectional"))
    )
    (net (code "19") (name "LED_BL") (class "Default")
      (node (ref "R14") (pin "2") (pinfunction "2_2") (pintype "bidirectional"))
      (node (ref "U1") (pin "12") (pinfunction "GPIO7_12") (pintype "bidirectional"))
    )
    (net (code "20") (name "LNA_IN") (class "Default")
      (node (ref "C36") (pin "1") (pinfunction "1_1") (pintype "passive"))
      (node (ref "U1") (pin "1") (pinfunction "LNA_IN_1") (pintype "bidirectional"))
    )
    (net (code "21") (name "LRCLK") (class "Default")
      (node (ref "IC8") (pin "C3") (pinfunction "LRCLK_C3") (pintype "bidirectional"))
      (node (ref "U1") (pin "43") (pinfunction "GPIO38_43") (pintype "bidirectional"))
    )
    (net (code "22") (name "LX1") (class "Default")
      (node (ref "IC9") (pin "B2") (pinfunction "SW1_1_B2") (pintype "bidirectional"))
      (node (ref "IC9") (pin "B3") (pinfunction "SW1_2_B3") (pintype "bidirectional"))
      (node (ref "L7") (pin "1") (pinfunction "1_1") (pintype "bidirectional"))
    )
    (net (code "23") (name "LX2") (class "Default")
      (node (ref "IC9") (pin "D2") (pinfunction "SW2_1_D2") (pintype "bidirectional"))
      (node (ref "IC9") (pin "D3") (pinfunction "SW2_2_D3") (pintype "bidirectional"))
      (node (ref "L7") (pin "2") (pinfunction "2_2") (pintype "bidirectional"))
    )
    (net (code "24") (name "LX3") (class "Default")
      (node (ref "IC3") (pin "B2") (pinfunction "SW1_1_B2") (pintype "bidirectional"))
      (node (ref "IC3") (pin "B3") (pinfunction "SW1_2_B3") (pintype "bidirectional"))
      (node (ref "L5") (pin "1") (pinfunction "1_1") (pintype "bidirectional"))
    )
    (net (code "25") (name "LX4") (class "Default")
      (node (ref "IC3") (pin "D2") (pinfunction "SW2_1_D2") (pintype "bidirectional"))
      (node (ref "IC3") (pin "D3") (pinfunction "SW2_2_D3") (pintype "bidirectional"))
      (node (ref "L5") (pin "2") (pinfunction "2_2") (pintype "bidirectional"))
    )
    (net (code "26") (name "Net-(ANT1-FEED)") (class "Default")
      (node (ref "ANT1") (pin "1") (pinfunction "FEED_1") (pintype "input"))
      (node (ref "L1") (pin "1") (pinfunction "1_1") (pintype "bidirectional"))
    )
    (net (code "27") (name "Net-(C32-Pad2)") (class "Default")
      (node (ref "C32") (pin "2") (pinfunction "2_2") (pintype "passive"))
      (node (ref "L3") (pin "1") (pinfunction "1_1") (pintype "bidirectional"))
      (node (ref "Y1") (pin "1") (pinfunction "1_1") (pintype "passive"))
    )
    (net (code "28") (name "Net-(C36-Pad2)") (class "Default")
      (node (ref "C36") (pin "2") (pinfunction "2_2") (pintype "passive"))
      (node (ref "L1") (pin "2") (pinfunction "2_2") (pintype "bidirectional"))
      (node (ref "L4") (pin "2") (pinfunction "2_2") (pintype "bidirectional"))
    )
    (net (code "29") (name "Net-(IC2-REG)") (class "Default")
      (node (ref "C27") (pin "2") (pinfunction "2_2") (pintype "passive"))
      (node (ref "IC2") (pin "A2") (pinfunction "REG_A2") (pintype "bidirectional"))
    )
    (net (code "30") (name "Net-(IC8-~{SD_MODE})") (class "Default")
      (node (ref "IC8") (pin "A1") (pinfunction "~{SD_MODE}_A1") (pintype "bidirectional"))
      (node (ref "R1") (pin "1") (pinfunction "1_1") (pintype "passive"))
    )
    (net (code "31") (name "Net-(Q1-G)") (class "Default")
      (node (ref "Q1") (pin "1") (pinfunction "G_1") (pintype "bidirectional"))
      (node (ref "R14") (pin "1") (pinfunction "1_1") (pintype "bidirectional"))
      (node (ref "R15") (pin "2") (pinfunction "2_2") (pintype "bidirectional"))
    )
    (net (code "32") (name "Net-(U1-U0TXD)") (class "Default")
      (node (ref "R2") (pin "1") (pinfunction "1_1") (pintype "bidirectional"))
      (node (ref "U1") (pin "49") (pinfunction "U0TXD_49") (pintype "bidirectional"))
    )
    (net (code "33") (name "OUT+") (class "Default")
      (node (ref "IC2") (pin "A3") (pinfunction "OUT+_A3") (pintype "bidirectional"))
      (node (ref "O+") (pin "TP") (pinfunction "TP_TP") (pintype "input"))
    )
    (net (code "34") (name "OUT-") (class "Default")
      (node (ref "IC2") (pin "C3") (pinfunction "OUT-_C3") (pintype "bidirectional"))
      (node (ref "O-") (pin "TP") (pinfunction "TP_TP") (pintype "input"))
    )
    (net (code "35") (name "OUTN") (class "Default")
      (node (ref "IC8") (pin "B3") (pinfunction "OUTN_B3") (pintype "bidirectional"))
      (node (ref "U$4") (pin "LEAD-") (pinfunction "LEAD-_LEAD-") (pintype "bidirectional"))
    )
    (net (code "36") (name "OUTP") (class "Default")
      (node (ref "IC8") (pin "A3") (pinfunction "OUTP_A3") (pintype "bidirectional"))
      (node (ref "U$4") (pin "LEAD+") (pinfunction "LEAD+_LEAD+") (pintype "bidirectional"))
    )
    (net (code "37") (name "PDM_CLK") (class "Default")
      (node (ref "U$6") (pin "CLK") (pinfunction "CLK_CLK") (pintype "bidirectional"))
      (node (ref "U1") (pin "48") (pinfunction "MTMS_48") (pintype "bidirectional"))
    )
    (net (code "38") (name "PDM_DATA") (class "Default")
      (node (ref "U$6") (pin "DATA") (pinfunction "DATA_DATA") (pintype "bidirectional"))
      (node (ref "U1") (pin "47") (pinfunction "MTDI_47") (pintype "bidirectional"))
    )
    (net (code "39") (name "RST") (class "Default")
      (node (ref "C17") (pin "2") (pinfunction "2_2") (pintype "passive"))
      (node (ref "R8") (pin "1") (pinfunction "1_1") (pintype "bidirectional"))
      (node (ref "U$3") (pin "P$1") (pinfunction "A_P$1") (pintype "bidirectional"))
      (node (ref "U1") (pin "4") (pinfunction "CHIP_PU_4") (pintype "input"))
    )
    (net (code "40") (name "RX") (class "Default")
      (node (ref "TP11") (pin "TP") (pinfunction "TP_TP") (pintype "input"))
      (node (ref "U1") (pin "50") (pinfunction "U0RXD_50") (pintype "bidirectional"))
    )
    (net (code "41") (name "SCL") (class "Default")
      (node (ref "IC1") (pin "13") (pinfunction "SCL_13") (pintype "bidirectional"))
      (node (ref "IC2") (pin "C1") (pinfunction "SCL_C1") (pintype "bidirectional"))
      (node (ref "IC3") (pin "D1") (pinfunction "SCL_D1") (pintype "bidirectional"))
      (node (ref "J1") (pin "15") (pinfunction "15_15") (pintype "bidirectional"))
      (node (ref "R13") (pin "2") (pinfunction "2_2") (pintype "bidirectional"))
      (node (ref "SCL") (pin "TP") (pinfunction "TP_TP") (pintype "input"))
      (node (ref "U1") (pin "14") (pinfunction "GPIO9_14") (pintype "bidirectional"))
      (node (ref "U4") (pin "7") (pinfunction "SCL_7") (pintype "input"))
    )
    (net (code "42") (name "SCL_DC") (class "Default")
      (node (ref "IC9") (pin "D1") (pinfunction "SCL_D1") (pintype "bidirectional"))
      (node (ref "R18") (pin "2") (pinfunction "2_2") (pintype "bidirectional"))
      (node (ref "SCL_DC") (pin "TP") (pinfunction "TP_TP") (pintype "input"))
    )
    (net (code "43") (name "SDA") (class "Default")
      (node (ref "IC1") (pin "14") (pinfunction "SDA_14") (pintype "bidirectional"))
      (node (ref "IC2") (pin "B2") (pinfunction "SDA_B2") (pintype "bidirectional"))
      (node (ref "IC3") (pin "E1") (pinfunction "SDA_E1") (pintype "bidirectional"))
      (node (ref "J1") (pin "14") (pinfunction "14_14") (pintype "bidirectional"))
      (node (ref "R12") (pin "2") (pinfunction "2_2") (pintype "bidirectional"))
      (node (ref "SDA") (pin "TP") (pinfunction "TP_TP") (pintype "input"))
      (node (ref "U1") (pin "13") (pinfunction "GPIO8_13") (pintype "bidirectional"))
      (node (ref "U4") (pin "8") (pinfunction "SDA_8") (pintype "bidirectional"))
    )
    (net (code "44") (name "SDA_DC") (class "Default")
      (node (ref "IC9") (pin "E1") (pinfunction "SDA_E1") (pintype "bidirectional"))
      (node (ref "R17") (pin "2") (pinfunction "2_2") (pintype "bidirectional"))
      (node (ref "SDA_DC") (pin "TP") (pinfunction "TP_TP") (pintype "input"))
    )
    (net (code "45") (name "SD_MODE") (class "Default")
      (node (ref "R1") (pin "2") (pinfunction "2_2") (pintype "passive"))
      (node (ref "U1") (pin "38") (pinfunction "GPIO33_38") (pintype "bidirectional"))
    )
    (net (code "46") (name "SPI2_CLK") (class "Default")
      (node (ref "IC4") (pin "6") (pinfunction "CLK_6") (pintype "bidirectional"))
      (node (ref "U1") (pin "41") (pinfunction "GPIO36_41") (pintype "bidirectional"))
    )
    (net (code "47") (name "SPI2_MISO") (class "Default")
      (node (ref "IC4") (pin "2") (pinfunction "DO_(IO1)_1_2") (pintype "bidirectional"))
      (node (ref "U1") (pin "42") (pinfunction "GPIO37_42") (pintype "bidirectional"))
    )
    (net (code "48") (name "SPI2_MOSI") (class "Default")
      (node (ref "IC4") (pin "5") (pinfunction "DI_(IO0)_5") (pintype "bidirectional"))
      (node (ref "U1") (pin "40") (pinfunction "GPIO35_40") (pintype "bidirectional"))
    )
    (net (code "49") (name "SPI3_CLK") (class "Default")
      (node (ref "J1") (pin "7") (pinfunction "7_7") (pintype "bidirectional"))
      (node (ref "U1") (pin "17") (pinfunction "GPIO12_17") (pintype "bidirectional"))
    )
    (net (code "50") (name "SPI3_MISO") (class "Default")
      (node (ref "U1") (pin "18") (pinfunction "GPIO13_18") (pintype "bidirectional"))
    )
    (net (code "51") (name "SPI3_MOSI") (class "Default")
      (node (ref "J1") (pin "8") (pinfunction "8_8") (pintype "bidirectional"))
      (node (ref "U1") (pin "16") (pinfunction "GPIO11_16") (pintype "bidirectional"))
    )
    (net (code "52") (name "SPICLK") (class "Default")
      (node (ref "IC7") (pin "6") (pinfunction "SCLK_6") (pintype "input"))
      (node (ref "U1") (pin "33") (pinfunction "SPICLK_33") (pintype "bidirectional"))
    )
    (net (code "53") (name "SPICS1") (class "Default")
      (node (ref "IC7") (pin "1") (pinfunction "CE#_1") (pintype "input"))
      (node (ref "U1") (pin "28") (pinfunction "SPICS1_28") (pintype "bidirectional"))
    )
    (net (code "54") (name "SPID") (class "Default")
      (node (ref "IC7") (pin "5") (pinfunction "SI/SIO[0]_5") (pintype "bidirectional"))
      (node (ref "U1") (pin "35") (pinfunction "SPID_35") (pintype "bidirectional"))
    )
    (net (code "55") (name "SPIHD") (class "Default")
      (node (ref "IC7") (pin "7") (pinfunction "SIO[3]_7") (pintype "bidirectional"))
      (node (ref "U1") (pin "30") (pinfunction "SPIHD_30") (pintype "bidirectional"))
    )
    (net (code "56") (name "SPIQ") (class "Default")
      (node (ref "IC7") (pin "2") (pinfunction "SO/SIO[1]_2") (pintype "bidirectional"))
      (node (ref "U1") (pin "34") (pinfunction "SPIQ_34") (pintype "bidirectional"))
    )
    (net (code "57") (name "SPIWP") (class "Default")
      (node (ref "IC7") (pin "3") (pinfunction "SIO[2]_3") (pintype "bidirectional"))
      (node (ref "U1") (pin "31") (pinfunction "SPIWP_31") (pintype "bidirectional"))
    )
    (net (code "58") (name "SS_FLASH") (class "Default")
      (node (ref "IC4") (pin "1") (pinfunction "/CS_1") (pintype "bidirectional"))
      (node (ref "U1") (pin "39") (pinfunction "GPIO34_39") (pintype "bidirectional"))
    )
    (net (code "59") (name "TFT_CS") (class "Default")
      (node (ref "J1") (pin "6") (pinfunction "6_6") (pintype "bidirectional"))
      (node (ref "U1") (pin "9") (pinfunction "GPIO4_9") (pintype "bidirectional"))
    )
    (net (code "60") (name "TFT_DC") (class "Default")
      (node (ref "J1") (pin "5") (pinfunction "5_5") (pintype "bidirectional"))
      (node (ref "U1") (pin "10") (pinfunction "GPIO5_10") (pintype "bidirectional"))
    )
    (net (code "61") (name "TFT_RST") (class "Default")
      (node (ref "J1") (pin "9") (pinfunction "9_9") (pintype "bidirectional"))
      (node (ref "U1") (pin "8") (pinfunction "GPIO3_8") (pintype "bidirectional"))
    )
    (net (code "62") (name "TP_INT") (class "Default")
      (node (ref "J1") (pin "13") (pinfunction "13_13") (pintype "bidirectional"))
      (node (ref "U1") (pin "6") (pinfunction "GPIO1_6") (pintype "bidirectional"))
    )
    (net (code "63") (name "TP_RST") (class "Default")
      (node (ref "J1") (pin "12") (pinfunction "12_12") (pintype "bidirectional"))
      (node (ref "U1") (pin "7") (pinfunction "GPIO2_7") (pintype "bidirectional"))
    )
    (net (code "64") (name "TS") (class "Default")
      (node (ref "R10") (pin "2") (pinfunction "2_2") (pintype "bidirectional"))
      (node (ref "U2") (pin "9") (pinfunction "TS_9") (pintype "input"))
    )
    (net (code "65") (name "TX") (class "Default")
      (node (ref "R2") (pin "2") (pinfunction "2_2") (pintype "bidirectional"))
      (node (ref "TP5") (pin "TP") (pinfunction "TP_TP") (pintype "input"))
    )
    (net (code "66") (name "VBAT") (class "Default")
      (node (ref "C26") (pin "2") (pinfunction "2_2") (pintype "passive"))
      (node (ref "C30") (pin "2") (pinfunction "2_2") (pintype "passive"))
      (node (ref "IC5") (pin "3") (pinfunction "D_3") (pintype "bidirectional"))
      (node (ref "TP1") (pin "TP") (pinfunction "TP_TP") (pintype "input"))
      (node (ref "U2") (pin "10") (pinfunction "OUT_10") (pintype "output"))
      (node (ref "U4") (pin "2") (pinfunction "CELL_2") (pintype "power_in"))
      (node (ref "U4") (pin "3") (pinfunction "VDD_3") (pintype "power_in"))
    )
    (net (code "67") (name "VBUS") (class "Default")
      (node (ref "C23") (pin "2") (pinfunction "2_2") (pintype "passive"))
      (node (ref "D1") (pin "1") (pinfunction "A_1") (pintype "bidirectional"))
      (node (ref "IC5") (pin "1") (pinfunction "G_1") (pintype "bidirectional"))
      (node (ref "R6") (pin "2") (pinfunction "2_2") (pintype "bidirectional"))
      (node (ref "U$5") (pin "A4B9") (pinfunction "VBUS_A4B9") (pintype "bidirectional"))
      (node (ref "U$5") (pin "B4A9") (pinfunction "VBUS1_B4A9") (pintype "bidirectional"))
      (node (ref "U2") (pin "1") (pinfunction "IN_1") (pintype "input"))
    )
    (net (code "68") (name "VDD3P3") (class "Default")
      (node (ref "C11") (pin "2") (pinfunction "2_2") (pintype "passive"))
      (node (ref "L2") (pin "1") (pinfunction "1_1") (pintype "passive"))
      (node (ref "RV1") (pin "1") (pinfunction "1_1") (pintype "bidirectional"))
      (node (ref "U1") (pin "2") (pinfunction "VDD3P3_2") (pintype "power_in"))
      (node (ref "U1") (pin "3") (pinfunction "VDD3P3_3") (pintype "power_in"))
    )
    (net (code "69") (name "VDD_SPI") (class "Default")
      (node (ref "C4") (pin "2") (pinfunction "2_2") (pintype "passive"))
      (node (ref "C5") (pin "2") (pinfunction "2_2") (pintype "passive"))
      (node (ref "IC7") (pin "8") (pinfunction "VCC_8") (pintype "power_in"))
      (node (ref "U1") (pin "29") (pinfunction "VDD_SPI_29") (pintype "power_in"))
    )
    (net (code "70") (name "VREG") (class "Default")
      (node (ref "C2") (pin "2") (pinfunction "2_2") (pintype "passive"))
      (node (ref "C20") (pin "2") (pinfunction "2_2") (pintype "passive"))
      (node (ref "C21") (pin "2") (pinfunction "2_2") (pintype "passive"))
      (node (ref "C34") (pin "2") (pinfunction "2_2") (pintype "passive"))
      (node (ref "D1") (pin "2") (pinfunction "K_2") (pintype "bidirectional"))
      (node (ref "IC3") (pin "A2") (pinfunction "VIN_1_A2") (pintype "bidirectional"))
      (node (ref "IC3") (pin "A3") (pinfunction "VIN_2_A3") (pintype "bidirectional"))
      (node (ref "IC5") (pin "2") (pinfunction "S_2") (pintype "bidirectional"))
      (node (ref "IC9") (pin "A1") (pinfunction "EN_A1") (pintype "bidirectional"))
      (node (ref "IC9") (pin "A2") (pinfunction "VIN_1_A2") (pintype "bidirectional"))
      (node (ref "IC9") (pin "A3") (pinfunction "VIN_2_A3") (pintype "bidirectional"))
      (node (ref "VREG") (pin "TP") (pinfunction "TP_TP") (pintype "input"))
    )
    (net (code "71") (name "XTAL_32K_N") (class "Default")
      (node (ref "C16") (pin "2") (pinfunction "2_2") (pintype "passive"))
      (node (ref "R4") (pin "2") (pinfunction "2_2") (pintype "bidirectional"))
      (node (ref "U1") (pin "22") (pinfunction "XTAL_32K_N_22") (pintype "bidirectional"))
      (node (ref "Y2") (pin "2") (pinfunction "2_2") (pintype "passive"))
    )
    (net (code "72") (name "XTAL_32K_P") (class "Default")
      (node (ref "C14") (pin "2") (pinfunction "2_2") (pintype "passive"))
      (node (ref "R4") (pin "1") (pinfunction "1_1") (pintype "bidirectional"))
      (node (ref "U1") (pin "21") (pinfunction "XTAL_32K_P_21") (pintype "bidirectional"))
      (node (ref "Y2") (pin "1") (pinfunction "1_1") (pintype "passive"))
    )
    (net (code "73") (name "XTAL_N") (class "Default")
      (node (ref "C13") (pin "2") (pinfunction "2_2") (pintype "passive"))
      (node (ref "U1") (pin "53") (pinfunction "XTAL_N_53") (pintype "output"))
      (node (ref "Y1") (pin "3") (pinfunction "2_3") (pintype "passive"))
    )
    (net (code "74") (name "XTAL_P") (class "Default")
      (node (ref "L3") (pin "2") (pinfunction "2_2") (pintype "bidirectional"))
      (node (ref "U1") (pin "54") (pinfunction "XTAL_P_54") (pintype "input"))
    )
    (net (code "75") (name "unconnected-(ANT1-NC-Pad2)") (class "Default")
      (node (ref "ANT1") (pin "2") (pinfunction "NC_2") (pintype "no_connect"))
    )
    (net (code "76") (name "unconnected-(IC1-NC_1-Pad10)") (class "Default")
      (node (ref "IC1") (pin "10") (pinfunction "NC_1_10") (pintype "bidirectional"))
    )
    (net (code "77") (name "unconnected-(IC1-NC_2-Pad11)") (class "Default")
      (node (ref "IC1") (pin "11") (pinfunction "NC_2_11") (pintype "bidirectional"))
    )
    (net (code "78") (name "unconnected-(J1-Pad16)") (class "Default")
      (node (ref "J1") (pin "16") (pinfunction "16_16") (pintype "bidirectional"))
    )
    (net (code "79") (name "unconnected-(J1-Pad17)") (class "Default")
      (node (ref "J1") (pin "17") (pinfunction "17_17") (pintype "bidirectional"))
    )
    (net (code "80") (name "unconnected-(U$4-DMY-PadDUMMY)") (class "Default")
      (node (ref "U$4") (pin "DUMMY") (pinfunction "DMY_DUMMY") (pintype "bidirectional"))
    )
    (net (code "81") (name "unconnected-(U$5-SUB1-PadA8)") (class "Default")
      (node (ref "U$5") (pin "A8") (pinfunction "SUB1_A8") (pintype "bidirectional"))
    )
    (net (code "82") (name "unconnected-(U$5-SUB2-PadB8)") (class "Default")
      (node (ref "U$5") (pin "B8") (pinfunction "SUB2_B8") (pintype "bidirectional"))
    )
    (net (code "83") (name "unconnected-(U1-GPIO6-Pad11)") (class "Default")
      (node (ref "U1") (pin "11") (pinfunction "GPIO6_11") (pintype "bidirectional"))
    )
    (net (code "84") (name "unconnected-(U1-GPIO45-Pad51)") (class "Default")
      (node (ref "U1") (pin "51") (pinfunction "GPIO45_51") (pintype "bidirectional"))
    )
    (net (code "85") (name "unconnected-(U1-GPIO46-Pad52)") (class "Default")
      (node (ref "U1") (pin "52") (pinfunction "GPIO46_52") (pintype "bidirectional"))
    )
    (net (code "86") (name "unconnected-(U1-SPICLK_N-Pad36)") (class "Default")
      (node (ref "U1") (pin "36") (pinfunction "SPICLK_N_36") (pintype "bidirectional"))
    )
    (net (code "87") (name "unconnected-(U1-SPICLK_P-Pad37)") (class "Default")
      (node (ref "U1") (pin "37") (pinfunction "SPICLK_P_37") (pintype "bidirectional"))
    )
    (net (code "88") (name "unconnected-(U1-SPICS0-Pad32)") (class "Default")
      (node (ref "U1") (pin "32") (pinfunction "SPICS0_32") (pintype "bidirectional"))
    )
    (net (code "89") (name "unconnected-(U2-PRETERM-Pad4)") (class "Default")
      (node (ref "U2") (pin "4") (pinfunction "PRETERM_4") (pintype "input"))
    )
    (net (code "90") (name "unconnected-(U2-~{PG}-Pad5)") (class "Default")
      (node (ref "U2") (pin "5") (pinfunction "~{PG}_5") (pintype "output"))
    )
  )
)
